# Com.net
KiCad netlist of a schematic drawn in Altium Designer
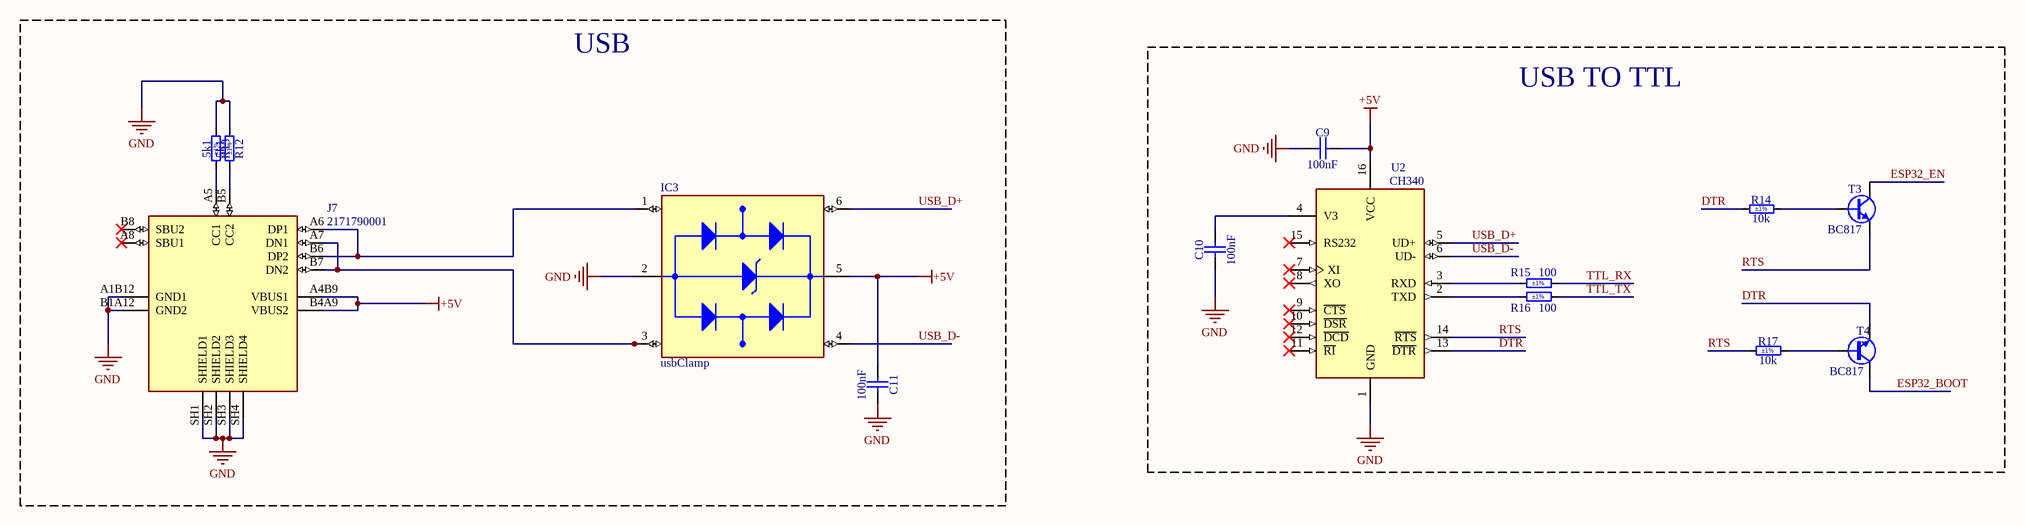
[diagram p0: Com.SchDoc]

(export (version "E")
  (design (tool "Eeschema 10.0.6"))
  (components
    (comp (ref "C9")
      (value "100nF")
      (footprint "CAPC1608X87N")
      (description "Non-polarised capacitor")
      (fields
        (field (name "PART NUMBER") "CC0603_100NF_50V_10%_X5R")
        (field (name "VOLTAGE") "50V")
        (field (name "AUTHOR") "CERN DEM MR")
      )
      (libsource (lib "Capacitors") (part "Capacitor - non polarized"))
    )
    (comp (ref "C10")
      (value "100nF")
      (footprint "CAPC1608X87N")
      (description "Non-polarised capacitor")
      (fields
        (field (name "PART NUMBER") "CC0603_100NF_50V_10%_X5R")
        (field (name "VOLTAGE") "50V")
        (field (name "AUTHOR") "CERN DEM MR")
      )
      (libsource (lib "Capacitors") (part "Capacitor - non polarized"))
    )
    (comp (ref "C11")
      (value "100nF")
      (footprint "CAPC1608X87N")
      (description "Non-polarised capacitor")
      (fields
        (field (name "PART NUMBER") "CC0603_100NF_50V_10%_X5R")
        (field (name "VOLTAGE") "50V")
        (field (name "AUTHOR") "CERN DEM MR")
      )
      (libsource (lib "Capacitors") (part "Capacitor - non polarized"))
    )
    (comp (ref "IC3")
      (value "usbClamp")
      (footprint "usbClamps")
      (libsource (lib "Schlib1") (part "usbClamp"))
    )
    (comp (ref "J7")
      (value "2171790001")
      (footprint "TYPEC")
      (libsource (lib "Tansa_Server_Schematic_Library") (part "TypeC USB2.0 16pin SMD"))
    )
    (comp (ref "R12")
      (value "5k1")
      (footprint "RESC1608X55N")
      (description "Resistor - 1%")
      (fields
        (field (name "TOLERANCE") "±1%")
        (field (name "PART NUMBER") "R0603_5K1_1%_0.1W_100PPM")
        (field (name "POWER") "0.1W")
        (field (name "AUTHOR") "CERN DEM JLC")
      )
      (libsource (lib "Resistors") (part "Resistor - 1%"))
    )
    (comp (ref "R13")
      (value "5k1")
      (footprint "RESC1608X55N")
      (description "Resistor - 1%")
      (fields
        (field (name "TOLERANCE") "±1%")
        (field (name "PART NUMBER") "R0603_5K1_1%_0.1W_100PPM")
        (field (name "POWER") "0.1W")
        (field (name "AUTHOR") "CERN DEM JLC")
      )
      (libsource (lib "Resistors") (part "Resistor - 1%"))
    )
    (comp (ref "R14")
      (value "10k")
      (footprint "RESC1608X55N")
      (description "Resistor - 1%")
      (fields
        (field (name "TOLERANCE") "±1%")
        (field (name "PART NUMBER") "R0603_10K_1%_0.1W_100PPM")
        (field (name "POWER") "0.1W")
        (field (name "AUTHOR") "CERN DEM JLC")
      )
      (libsource (lib "Resistors") (part "Resistor - 1%"))
    )
    (comp (ref "R15")
      (value "100")
      (footprint "RESC1608X55N")
      (description "Resistor - 1%")
      (fields
        (field (name "TOLERANCE") "±1%")
        (field (name "PART NUMBER") "R0603_100R_1%_0.1W_100PPM")
        (field (name "POWER") "0.1W")
        (field (name "AUTHOR") "CERN DEM JLC")
      )
      (libsource (lib "Resistors") (part "Resistor - 1%"))
    )
    (comp (ref "R16")
      (value "100")
      (footprint "RESC1608X55N")
      (description "Resistor - 1%")
      (fields
        (field (name "TOLERANCE") "±1%")
        (field (name "PART NUMBER") "R0603_100R_1%_0.1W_100PPM")
        (field (name "POWER") "0.1W")
        (field (name "AUTHOR") "CERN DEM JLC")
      )
      (libsource (lib "Resistors") (part "Resistor - 1%"))
    )
    (comp (ref "R17")
      (value "10k")
      (footprint "RESC1608X55N")
      (description "Resistor - 1%")
      (fields
        (field (name "TOLERANCE") "±1%")
        (field (name "PART NUMBER") "R0603_10K_1%_0.1W_100PPM")
        (field (name "POWER") "0.1W")
        (field (name "AUTHOR") "CERN DEM JLC")
      )
      (libsource (lib "Resistors") (part "Resistor - 1%"))
    )
    (comp (ref "T3")
      (value "BC817")
      (footprint "SOT95P230X110-3N")
      (description "NPN Transistor")
      (fields (field (name "MANUFACTURER") "NXP SEMICONDUCTORS") (field (name "AUTHOR") "CERN DEM JLC"))
      (libsource (lib "ICs And Semiconductors") (part "NPN B1 E2 C3"))
    )
    (comp (ref "T4")
      (value "BC817")
      (footprint "SOT95P230X110-3N")
      (description "NPN Transistor")
      (fields (field (name "MANUFACTURER") "NXP SEMICONDUCTORS") (field (name "AUTHOR") "CERN DEM JLC"))
      (libsource (lib "ICs And Semiconductors") (part "NPN B1 E2 C3"))
    )
    (comp (ref "U2") (value "CH340") (footprint "CH340") (libsource (lib "Schlib1") (part "CH340")))
  )
  (nets
    (net (code "1") (name "+5V") (class "Default")
      (node (ref "C11") (pin "2") (pinfunction "2_2") (pintype "passive"))
      (node (ref "C9") (pin "2") (pinfunction "2_2") (pintype "passive"))
      (node (ref "IC3") (pin "5") (pinfunction "VBUS_5") (pintype "power_in"))
      (node (ref "J7") (pin "A4B9") (pinfunction "VBUS1_A4B9") (pintype "power_in"))
      (node (ref "J7") (pin "B4A9") (pinfunction "VBUS2_B4A9") (pintype "power_in"))
      (node (ref "U2") (pin "16") (pinfunction "VCC_16") (pintype "power_in"))
    )
    (net (code "2") (name "/DTR") (class "Default")
      (node (ref "R14") (pin "1") (pinfunction "1_1") (pintype "passive"))
      (node (ref "T4") (pin "2") (pinfunction "E_2") (pintype "passive"))
      (node (ref "U2") (pin "13") (pinfunction "~{DTR}_13") (pintype "output"))
    )
    (net (code "3") (name "/ESP32_BOOT") (class "Default")
      (node (ref "T4") (pin "3") (pinfunction "C_3") (pintype "passive"))
    )
    (net (code "4") (name "/ESP32_EN") (class "Default")
      (node (ref "T3") (pin "3") (pinfunction "C_3") (pintype "passive"))
    )
    (net (code "5") (name "/RTS") (class "Default")
      (node (ref "R17") (pin "1") (pinfunction "1_1") (pintype "passive"))
      (node (ref "T3") (pin "2") (pinfunction "E_2") (pintype "passive"))
      (node (ref "U2") (pin "14") (pinfunction "~{RTS}_14") (pintype "output"))
    )
    (net (code "6") (name "/TTL_RX") (class "Default")
      (node (ref "R15") (pin "2") (pinfunction "2_2") (pintype "passive"))
    )
    (net (code "7") (name "/TTL_TX") (class "Default")
      (node (ref "R16") (pin "2") (pinfunction "2_2") (pintype "passive"))
    )
    (net (code "8") (name "/USB_D+") (class "Default")
      (node (ref "IC3") (pin "6") (pinfunction "I/O1_OUT_6") (pintype "bidirectional"))
      (node (ref "U2") (pin "5") (pinfunction "UD+_5") (pintype "bidirectional"))
    )
    (net (code "9") (name "/USB_D-") (class "Default")
      (node (ref "IC3") (pin "4") (pinfunction "I/O2_OUT_4") (pintype "bidirectional"))
      (node (ref "U2") (pin "6") (pinfunction "UD-_6") (pintype "bidirectional"))
    )
    (net (code "10") (name "GND") (class "Default")
      (node (ref "C10") (pin "1") (pinfunction "1_1") (pintype "passive"))
      (node (ref "C11") (pin "1") (pinfunction "1_1") (pintype "passive"))
      (node (ref "C9") (pin "1") (pinfunction "1_1") (pintype "passive"))
      (node (ref "IC3") (pin "2") (pinfunction "GND_2") (pintype "power_in"))
      (node (ref "J7") (pin "A1B12") (pinfunction "GND1_A1B12") (pintype "power_in"))
      (node (ref "J7") (pin "B1A12") (pinfunction "GND2_B1A12") (pintype "power_in"))
      (node (ref "J7") (pin "SH1") (pinfunction "SHIELD1_SH1") (pintype "passive"))
      (node (ref "J7") (pin "SH2") (pinfunction "SHIELD2_SH2") (pintype "passive"))
      (node (ref "J7") (pin "SH3") (pinfunction "SHIELD3_SH3") (pintype "passive"))
      (node (ref "J7") (pin "SH4") (pinfunction "SHIELD4_SH4") (pintype "passive"))
      (node (ref "R12") (pin "2") (pinfunction "2_2") (pintype "passive"))
      (node (ref "R13") (pin "2") (pinfunction "2_2") (pintype "passive"))
      (node (ref "U2") (pin "1") (pinfunction "GND_1") (pintype "power_in"))
    )
    (net (code "11") (name "Net-(IC3-I{slash}O1_IN)") (class "Default")
      (node (ref "IC3") (pin "1") (pinfunction "I/O1_IN_1") (pintype "bidirectional"))
      (node (ref "J7") (pin "A6") (pinfunction "DP1_A6") (pintype "bidirectional"))
      (node (ref "J7") (pin "B6") (pinfunction "DP2_B6") (pintype "bidirectional"))
    )
    (net (code "12") (name "Net-(IC3-I{slash}O2_IN)") (class "Default")
      (node (ref "IC3") (pin "3") (pinfunction "I/O2_IN_3") (pintype "bidirectional"))
      (node (ref "J7") (pin "A7") (pinfunction "DN1_A7") (pintype "bidirectional"))
      (node (ref "J7") (pin "B7") (pinfunction "DN2_B7") (pintype "bidirectional"))
    )
    (net (code "13") (name "Net-(J7-CC1)") (class "Default")
      (node (ref "J7") (pin "A5") (pinfunction "CC1_A5") (pintype "bidirectional"))
      (node (ref "R13") (pin "1") (pinfunction "1_1") (pintype "passive"))
    )
    (net (code "14") (name "Net-(J7-CC2)") (class "Default")
      (node (ref "J7") (pin "B5") (pinfunction "CC2_B5") (pintype "bidirectional"))
      (node (ref "R12") (pin "1") (pinfunction "1_1") (pintype "passive"))
    )
    (net (code "15") (name "Net-(T3-B)") (class "Default")
      (node (ref "R14") (pin "2") (pinfunction "2_2") (pintype "passive"))
      (node (ref "T3") (pin "1") (pinfunction "B_1") (pintype "passive"))
    )
    (net (code "16") (name "Net-(T4-B)") (class "Default")
      (node (ref "R17") (pin "2") (pinfunction "2_2") (pintype "passive"))
      (node (ref "T4") (pin "1") (pinfunction "B_1") (pintype "passive"))
    )
    (net (code "17") (name "Net-(U2-RXD)") (class "Default")
      (node (ref "R15") (pin "1") (pinfunction "1_1") (pintype "passive"))
      (node (ref "U2") (pin "3") (pinfunction "RXD_3") (pintype "input"))
    )
    (net (code "18") (name "Net-(U2-TXD)") (class "Default")
      (node (ref "R16") (pin "1") (pinfunction "1_1") (pintype "passive"))
      (node (ref "U2") (pin "2") (pinfunction "TXD_2") (pintype "output"))
    )
    (net (code "19") (name "Net-(U2-V3)") (class "Default")
      (node (ref "C10") (pin "2") (pinfunction "2_2") (pintype "passive"))
      (node (ref "U2") (pin "4") (pinfunction "V3_4") (pintype "power_in"))
    )
    (net (code "20") (name "unconnected-(J7-SBU1-PadA8)") (class "Default")
      (node (ref "J7") (pin "A8") (pinfunction "SBU1_A8") (pintype "bidirectional+no_connect"))
    )
    (net (code "21") (name "unconnected-(J7-SBU2-PadB8)") (class "Default")
      (node (ref "J7") (pin "B8") (pinfunction "SBU2_B8") (pintype "bidirectional+no_connect"))
    )
    (net (code "22") (name "unconnected-(U2-RS232-Pad15)") (class "Default")
      (node (ref "U2") (pin "15") (pinfunction "RS232_15") (pintype "input+no_connect"))
    )
    (net (code "23") (name "unconnected-(U2-XI-Pad7)") (class "Default")
      (node (ref "U2") (pin "7") (pinfunction "XI_7") (pintype "input+no_connect"))
    )
    (net (code "24") (name "unconnected-(U2-XO-Pad8)") (class "Default")
      (node (ref "U2") (pin "8") (pinfunction "XO_8") (pintype "output+no_connect"))
    )
    (net (code "25") (name "unconnected-(U2-~{CTS}-Pad9)") (class "Default")
      (node (ref "U2") (pin "9") (pinfunction "~{CTS}_9") (pintype "input+no_connect"))
    )
    (net (code "26") (name "unconnected-(U2-~{DCD}-Pad12)") (class "Default")
      (node (ref "U2") (pin "12") (pinfunction "~{DCD}_12") (pintype "input+no_connect"))
    )
    (net (code "27") (name "unconnected-(U2-~{DSR}-Pad10)") (class "Default")
      (node (ref "U2") (pin "10") (pinfunction "~{DSR}_10") (pintype "input+no_connect"))
    )
    (net (code "28") (name "unconnected-(U2-~{RI}-Pad11)") (class "Default")
      (node (ref "U2") (pin "11") (pinfunction "~{RI}_11") (pintype "input+no_connect"))
    )
  )
)
